# SCH_USB_Aris_2025-03-20.net
KiCad netlist of a schematic drawn in EasyEDA
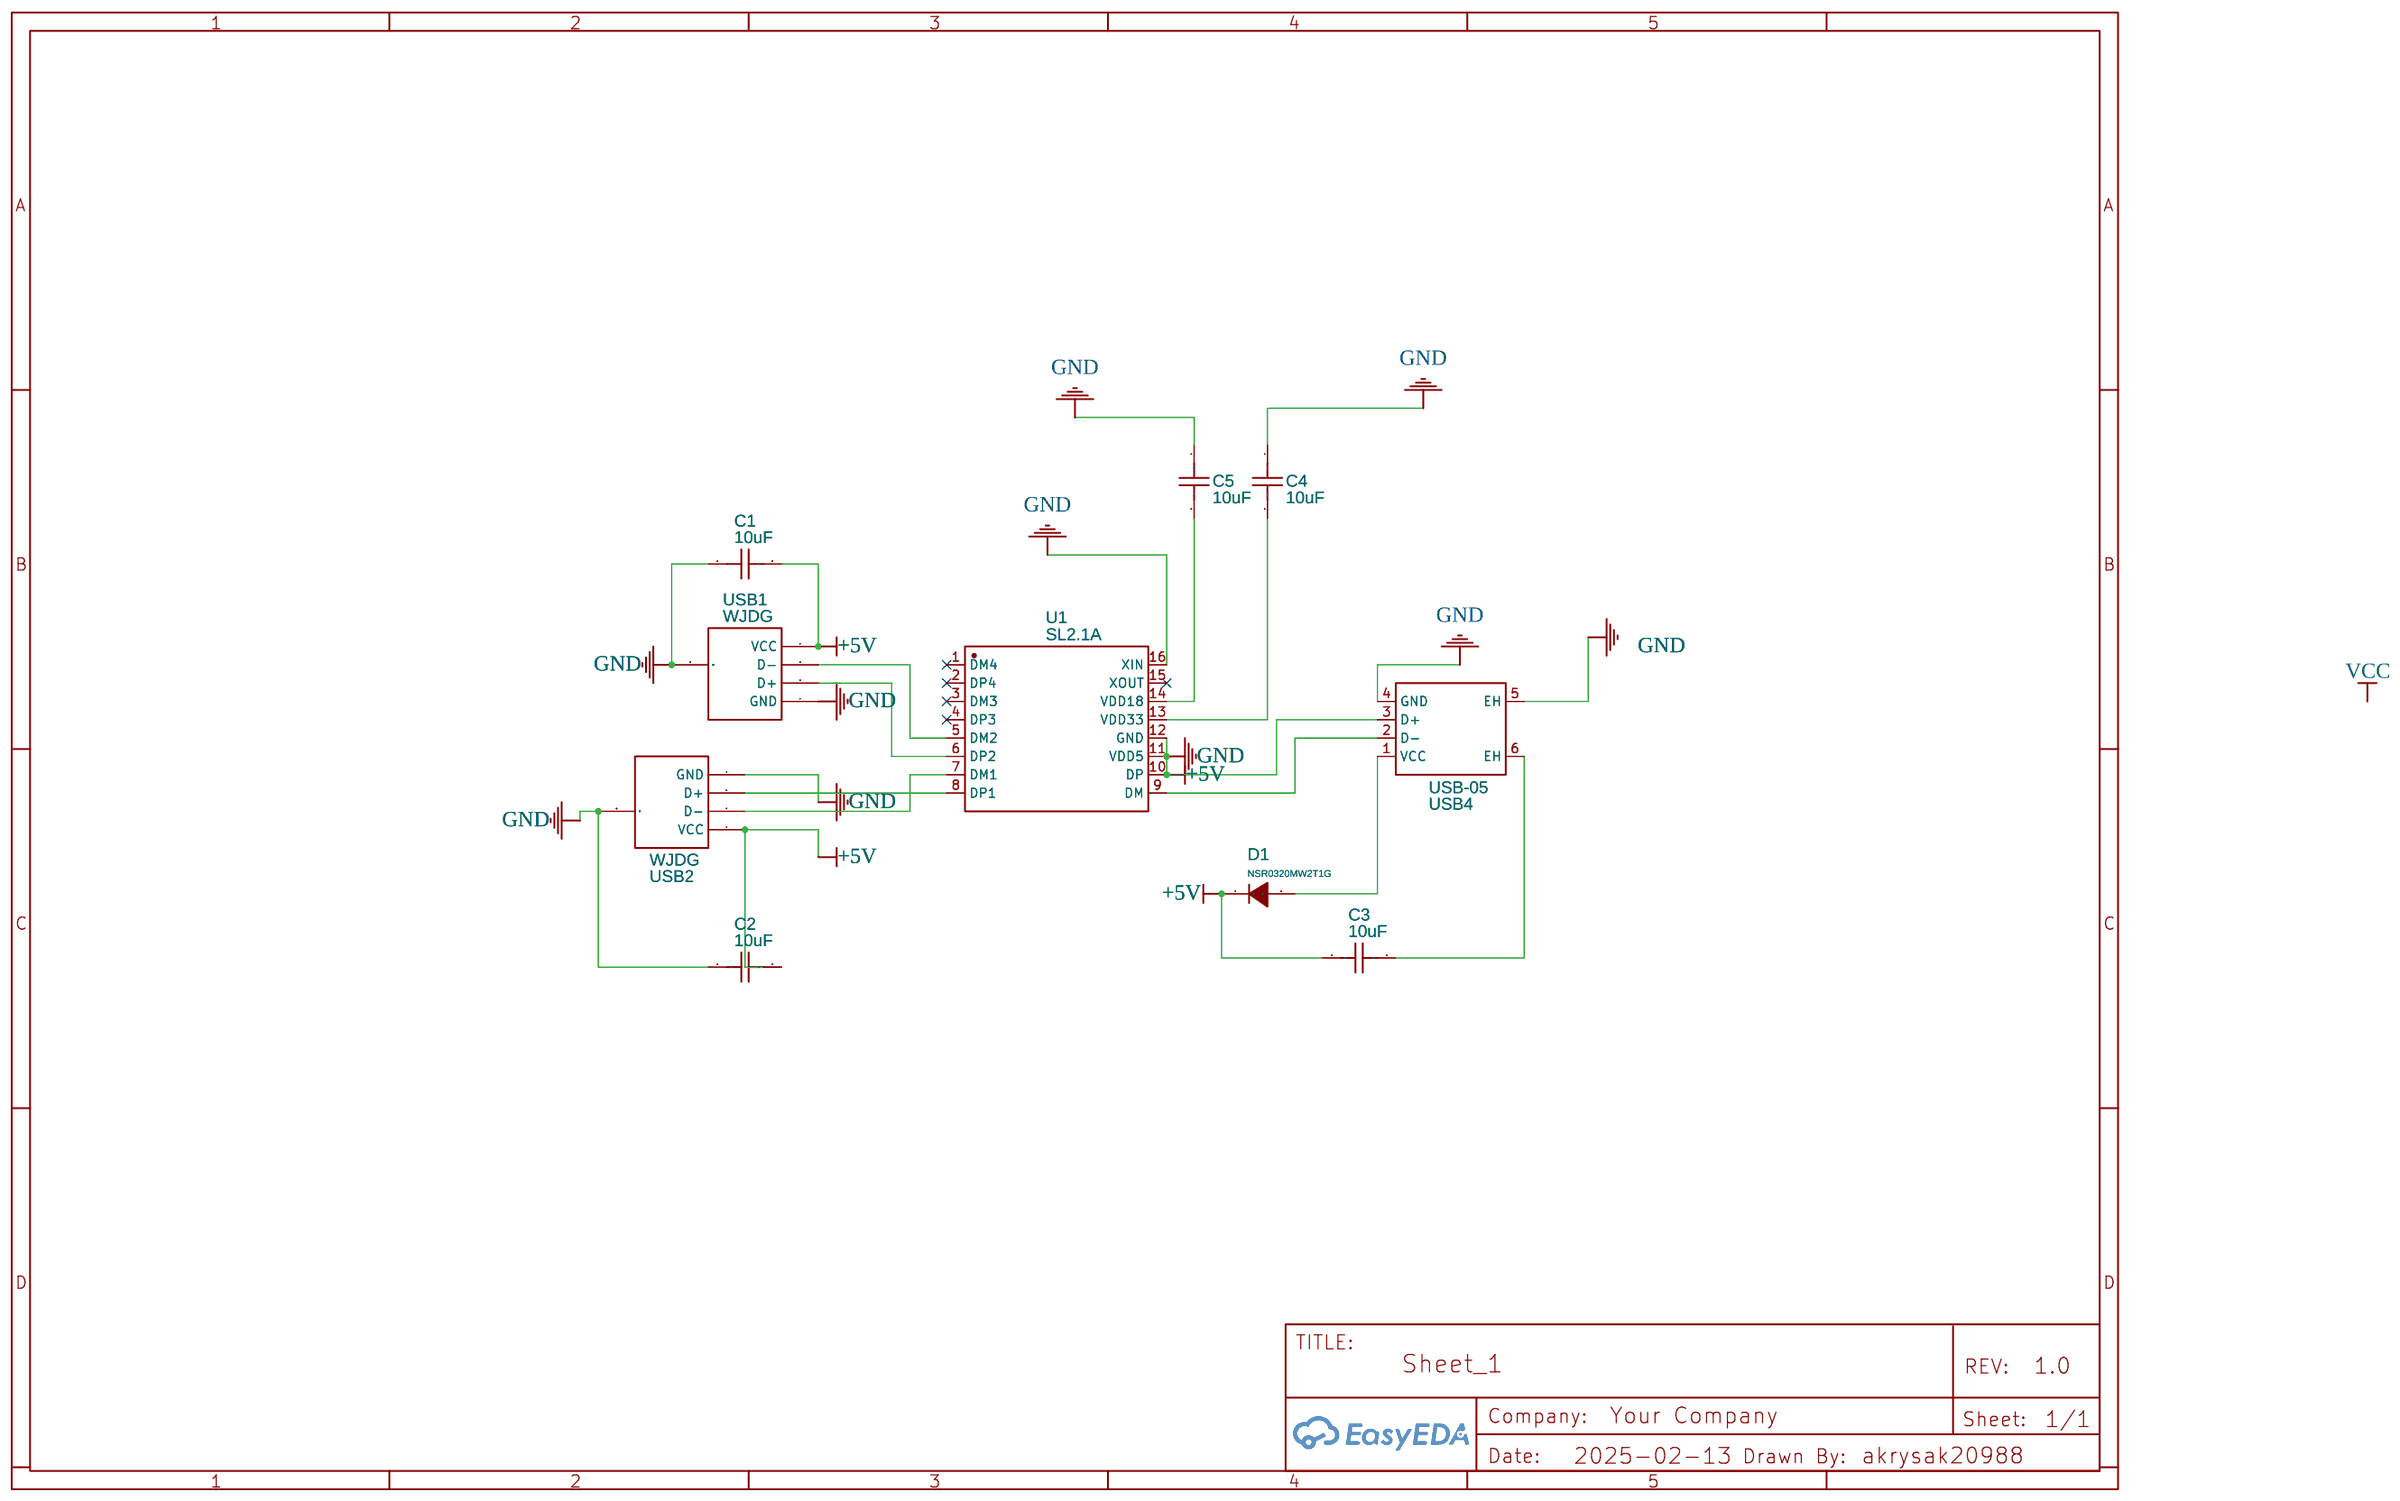
[diagram p0: schematic sheet]

(export (version "E")
  (design (tool "Eeschema 10.0.6"))
  (components
    (comp (ref "C1")
      (value "10uF")
      (fields
        (field (name "Manufacturer Part") "CL10A106KP8NNNC")
        (field (name "Manufacturer") "SAMSUNG(三星)")
      )
      (libsource (lib "") (part "CL10A106KP8NNNC"))
    )
    (comp (ref "C2")
      (value "10uF")
      (fields
        (field (name "Manufacturer Part") "CL10A106KP8NNNC")
        (field (name "Manufacturer") "SAMSUNG(三星)")
      )
      (libsource (lib "") (part "CL10A106KP8NNNC"))
    )
    (comp (ref "C3")
      (value "10uF")
      (fields
        (field (name "Manufacturer Part") "CL10A106KP8NNNC")
        (field (name "Manufacturer") "SAMSUNG(三星)")
      )
      (libsource (lib "") (part "CL10A106KP8NNNC"))
    )
    (comp (ref "C4")
      (value "10uF")
      (fields
        (field (name "Manufacturer Part") "CL10A106KP8NNNC")
        (field (name "Manufacturer") "SAMSUNG(三星)")
      )
      (libsource (lib "") (part "CL10A106KP8NNNC_1"))
    )
    (comp (ref "C5")
      (value "10uF")
      (fields
        (field (name "Manufacturer Part") "CL10A106KP8NNNC")
        (field (name "Manufacturer") "SAMSUNG(三星)")
      )
      (libsource (lib "") (part "CL10A106KP8NNNC_1"))
    )
    (comp (ref "D1")
      (value "NSR0320MW2T1G")
      (fields (field (name "Manufacturer") "onsemi(安森美)"))
      (libsource (lib "") (part "NSR0320MW2T1G"))
    )
    (comp (ref "U1")
      (value "SL2.1A")
      (fields (field (name "Manufacturer") "CoreChips(和芯润德)"))
      (libsource (lib "") (part "SL2.1A"))
    )
    (comp (ref "USB1")
      (value "WJDG")
      (fields (field (name "Manufacturer Part") "AF 90° WJDG") (field (name "Manufacturer") "SHOU HAN(首韩)"))
      (libsource (lib "") (part "AF 90° WJDG"))
    )
    (comp (ref "USB2")
      (value "WJDG")
      (fields (field (name "Manufacturer Part") "AF 90° WJDG") (field (name "Manufacturer") "SHOU HAN(首韩)"))
      (libsource (lib "") (part "AF 90° WJDG_1"))
    )
    (comp (ref "USB4")
      (value "USB-05")
      (fields (field (name "Manufacturer") "SOFNG(硕方)"))
      (libsource (lib "") (part "USB-05"))
    )
  )
  (nets
    (net (code "1") (name "+5V") (class "Default")
      (node (ref "C1") (pin "1") (pinfunction "1_1") (pintype "unspecified"))
      (node (ref "C1") (pin "2") (pinfunction "2_2") (pintype "unspecified"))
      (node (ref "C2") (pin "1") (pinfunction "1_1") (pintype "unspecified"))
      (node (ref "C2") (pin "2") (pinfunction "2_2") (pintype "unspecified"))
      (node (ref "C3") (pin "1") (pinfunction "1_1") (pintype "unspecified"))
      (node (ref "C4") (pin "1") (pinfunction "1_1") (pintype "unspecified"))
      (node (ref "C5") (pin "1") (pinfunction "1_1") (pintype "unspecified"))
      (node (ref "D1") (pin "1") (pinfunction "C_1") (pintype "unspecified"))
      (node (ref "U1") (pin "10") (pinfunction "DP_10") (pintype "unspecified"))
      (node (ref "U1") (pin "11") (pinfunction "VDD5_11") (pintype "unspecified"))
      (node (ref "U1") (pin "12") (pinfunction "GND_12") (pintype "unspecified"))
      (node (ref "U1") (pin "16") (pinfunction "XIN_16") (pintype "unspecified"))
      (node (ref "USB1") (pin "1") (pinfunction "VCC_1") (pintype "input"))
      (node (ref "USB1") (pin "4") (pinfunction "GND_4") (pintype "input"))
      (node (ref "USB1") (pin "5") (pinfunction "SHLD_5") (pintype "unspecified"))
      (node (ref "USB2") (pin "1") (pinfunction "VCC_1") (pintype "input"))
      (node (ref "USB2") (pin "4") (pinfunction "GND_4") (pintype "input"))
      (node (ref "USB2") (pin "5") (pinfunction "SHLD_5") (pintype "unspecified"))
      (node (ref "USB4") (pin "3") (pinfunction "D+_3") (pintype "input"))
      (node (ref "USB4") (pin "4") (pinfunction "GND_4") (pintype "input"))
      (node (ref "USB4") (pin "5") (pinfunction "EH_5") (pintype "unspecified"))
    )
    (net (code "2") (name "Net-(C3-Pad2)") (class "Default")
      (node (ref "C3") (pin "2") (pinfunction "2_2") (pintype "unspecified"))
      (node (ref "USB4") (pin "6") (pinfunction "EH_6") (pintype "unspecified"))
    )
    (net (code "3") (name "Net-(D1-A)") (class "Default")
      (node (ref "D1") (pin "2") (pinfunction "A_2") (pintype "unspecified"))
      (node (ref "USB4") (pin "1") (pinfunction "VCC_1") (pintype "input"))
    )
    (net (code "4") (name "Net-(U1-DM)") (class "Default")
      (node (ref "U1") (pin "9") (pinfunction "DM_9") (pintype "unspecified"))
      (node (ref "USB4") (pin "2") (pinfunction "D-_2") (pintype "input"))
    )
    (net (code "5") (name "Net-(U1-DM1)") (class "Default")
      (node (ref "U1") (pin "7") (pinfunction "DM1_7") (pintype "unspecified"))
      (node (ref "USB2") (pin "2") (pinfunction "D-_2") (pintype "input"))
    )
    (net (code "6") (name "Net-(U1-DM2)") (class "Default")
      (node (ref "U1") (pin "5") (pinfunction "DM2_5") (pintype "unspecified"))
      (node (ref "USB1") (pin "2") (pinfunction "D-_2") (pintype "input"))
    )
    (net (code "7") (name "Net-(U1-DP1)") (class "Default")
      (node (ref "U1") (pin "8") (pinfunction "DP1_8") (pintype "unspecified"))
      (node (ref "USB2") (pin "3") (pinfunction "D+_3") (pintype "input"))
    )
    (net (code "8") (name "Net-(U1-DP2)") (class "Default")
      (node (ref "U1") (pin "6") (pinfunction "DP2_6") (pintype "unspecified"))
      (node (ref "USB1") (pin "3") (pinfunction "D+_3") (pintype "input"))
    )
    (net (code "9") (name "Net-(U1-VDD18)") (class "Default")
      (node (ref "C5") (pin "2") (pinfunction "2_2") (pintype "unspecified"))
      (node (ref "U1") (pin "14") (pinfunction "VDD18_14") (pintype "unspecified"))
    )
    (net (code "10") (name "Net-(U1-VDD33)") (class "Default")
      (node (ref "C4") (pin "2") (pinfunction "2_2") (pintype "unspecified"))
      (node (ref "U1") (pin "13") (pinfunction "VDD33_13") (pintype "unspecified"))
    )
    (net (code "12") (name "unconnected-(U1-DM3-Pad3)") (class "Default")
      (node (ref "U1") (pin "3") (pinfunction "DM3_3") (pintype "unspecified+no_connect"))
    )
    (net (code "13") (name "unconnected-(U1-DM4-Pad1)") (class "Default")
      (node (ref "U1") (pin "1") (pinfunction "DM4_1") (pintype "unspecified+no_connect"))
    )
    (net (code "14") (name "unconnected-(U1-DP3-Pad4)") (class "Default")
      (node (ref "U1") (pin "4") (pinfunction "DP3_4") (pintype "unspecified+no_connect"))
    )
    (net (code "15") (name "unconnected-(U1-DP4-Pad2)") (class "Default")
      (node (ref "U1") (pin "2") (pinfunction "DP4_2") (pintype "unspecified+no_connect"))
    )
    (net (code "16") (name "unconnected-(U1-XOUT-Pad15)") (class "Default")
      (node (ref "U1") (pin "15") (pinfunction "XOUT_15") (pintype "unspecified+no_connect"))
    )
  )
)
